# SCH_Driver_Key_PCB_3_5_3_8_5_0_2022-07-1.net
KiCad netlist of a schematic drawn in EasyEDA
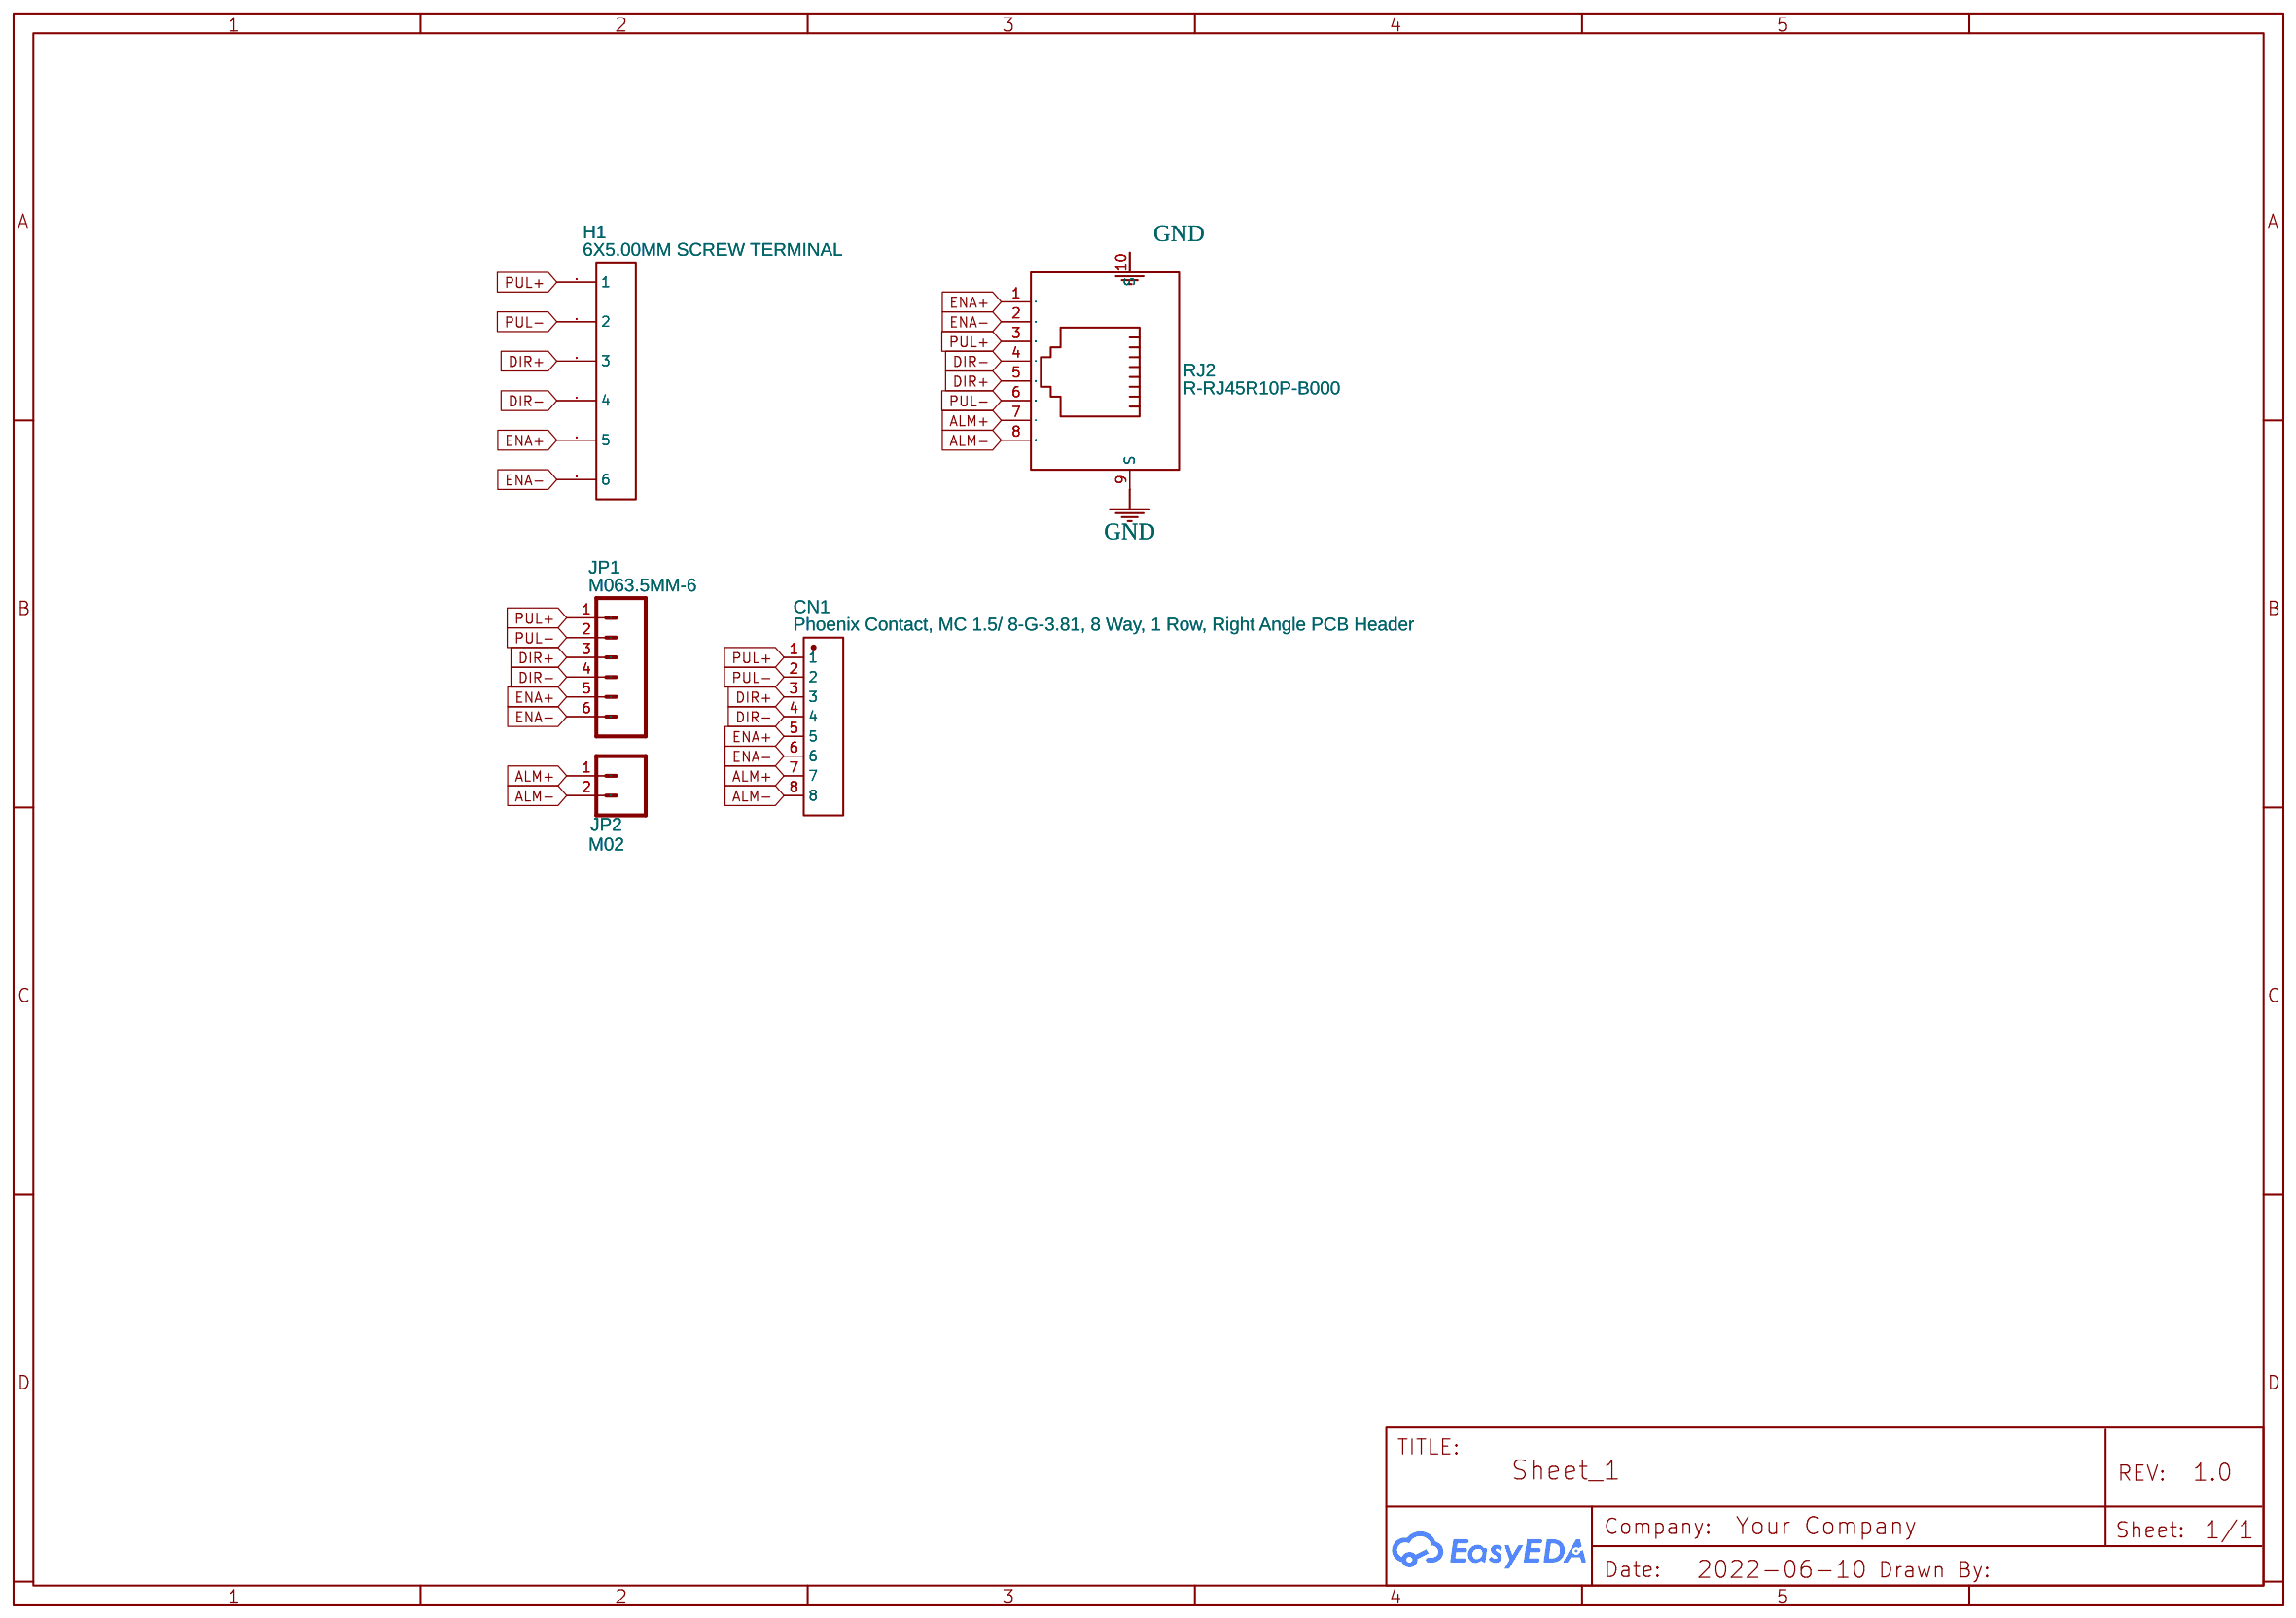
[diagram p0: schematic sheet]

(export (version "E")
  (design (tool "Eeschema 10.0.6"))
  (components
    (comp (ref "CN1")
      (value "Phoenix Contact, MC 1.5/ 8-G-3.81, 8 Way, 1 Row, Right Angle PCB Header")
      (fields (field (name "BOM_Manufacturer Part") "1803332") (field (name "BOM_Supplier Part") "220-4793"))
      (libsource (lib "") (part "Phoenix Contact, MC 1.5/ 8-G-3.81, 8 Way, 1 Row, Right Angle PCB Header"))
    )
    (comp (ref "H1") (value "6X5.00MM SCREW TERMINAL") (libsource (lib "") (part "6X5.00MM SCREW TERMINAL")))
    (comp (ref "JP1") (value "M063.5MM-6") (libsource (lib "") (part "M063.5MM-6")))
    (comp (ref "JP2") (value "M02") (libsource (lib "") (part "M02")))
    (comp (ref "RJ2")
      (value "R-RJ45R10P-B000")
      (fields (field (name "BOM_Supplier Part") "C386758"))
      (libsource (lib "") (part "R-RJ45R10P-B000"))
    )
  )
  (nets
    (net (code "1") (name "ALM+") (class "Default")
      (node (ref "CN1") (pin "7") (pinfunction "7_7") (pintype "unspecified"))
      (node (ref "JP2") (pin "1") (pinfunction "1_1") (pintype "unspecified"))
      (node (ref "RJ2") (pin "7") (pinfunction "7_7") (pintype "unspecified"))
    )
    (net (code "2") (name "ALM-") (class "Default")
      (node (ref "CN1") (pin "8") (pinfunction "8_8") (pintype "unspecified"))
      (node (ref "JP2") (pin "2") (pinfunction "2_2") (pintype "unspecified"))
      (node (ref "RJ2") (pin "8") (pinfunction "8_8") (pintype "unspecified"))
    )
    (net (code "3") (name "DIR+") (class "Default")
      (node (ref "CN1") (pin "3") (pinfunction "3_3") (pintype "unspecified"))
      (node (ref "H1") (pin "3") (pinfunction "3_3") (pintype "unspecified"))
      (node (ref "JP1") (pin "3") (pinfunction "3_3") (pintype "unspecified"))
      (node (ref "RJ2") (pin "5") (pinfunction "5_5") (pintype "unspecified"))
    )
    (net (code "4") (name "DIR-") (class "Default")
      (node (ref "CN1") (pin "4") (pinfunction "4_4") (pintype "unspecified"))
      (node (ref "H1") (pin "4") (pinfunction "4_4") (pintype "unspecified"))
      (node (ref "JP1") (pin "4") (pinfunction "4_4") (pintype "unspecified"))
      (node (ref "RJ2") (pin "4") (pinfunction "4_4") (pintype "unspecified"))
    )
    (net (code "5") (name "ENA+") (class "Default")
      (node (ref "CN1") (pin "5") (pinfunction "5_5") (pintype "unspecified"))
      (node (ref "H1") (pin "5") (pinfunction "5_5") (pintype "unspecified"))
      (node (ref "JP1") (pin "5") (pinfunction "5_5") (pintype "unspecified"))
      (node (ref "RJ2") (pin "1") (pinfunction "1_1") (pintype "unspecified"))
    )
    (net (code "6") (name "ENA-") (class "Default")
      (node (ref "CN1") (pin "6") (pinfunction "6_6") (pintype "unspecified"))
      (node (ref "H1") (pin "6") (pinfunction "6_6") (pintype "unspecified"))
      (node (ref "JP1") (pin "6") (pinfunction "6_6") (pintype "unspecified"))
      (node (ref "RJ2") (pin "2") (pinfunction "2_2") (pintype "unspecified"))
    )
    (net (code "7") (name "GND") (class "Default")
      (node (ref "RJ2") (pin "10") (pinfunction "S_10") (pintype "unspecified"))
      (node (ref "RJ2") (pin "9") (pinfunction "S_9") (pintype "unspecified"))
    )
    (net (code "8") (name "PUL+") (class "Default")
      (node (ref "CN1") (pin "1") (pinfunction "1_1") (pintype "unspecified"))
      (node (ref "H1") (pin "1") (pinfunction "1_1") (pintype "unspecified"))
      (node (ref "JP1") (pin "1") (pinfunction "1_1") (pintype "unspecified"))
      (node (ref "RJ2") (pin "3") (pinfunction "3_3") (pintype "unspecified"))
    )
    (net (code "9") (name "PUL-") (class "Default")
      (node (ref "CN1") (pin "2") (pinfunction "2_2") (pintype "unspecified"))
      (node (ref "H1") (pin "2") (pinfunction "2_2") (pintype "unspecified"))
      (node (ref "JP1") (pin "2") (pinfunction "2_2") (pintype "unspecified"))
      (node (ref "RJ2") (pin "6") (pinfunction "6_6") (pintype "unspecified"))
    )
  )
)
